# Encoder_Interface.net
KiCad netlist of a schematic drawn in Altium Designer
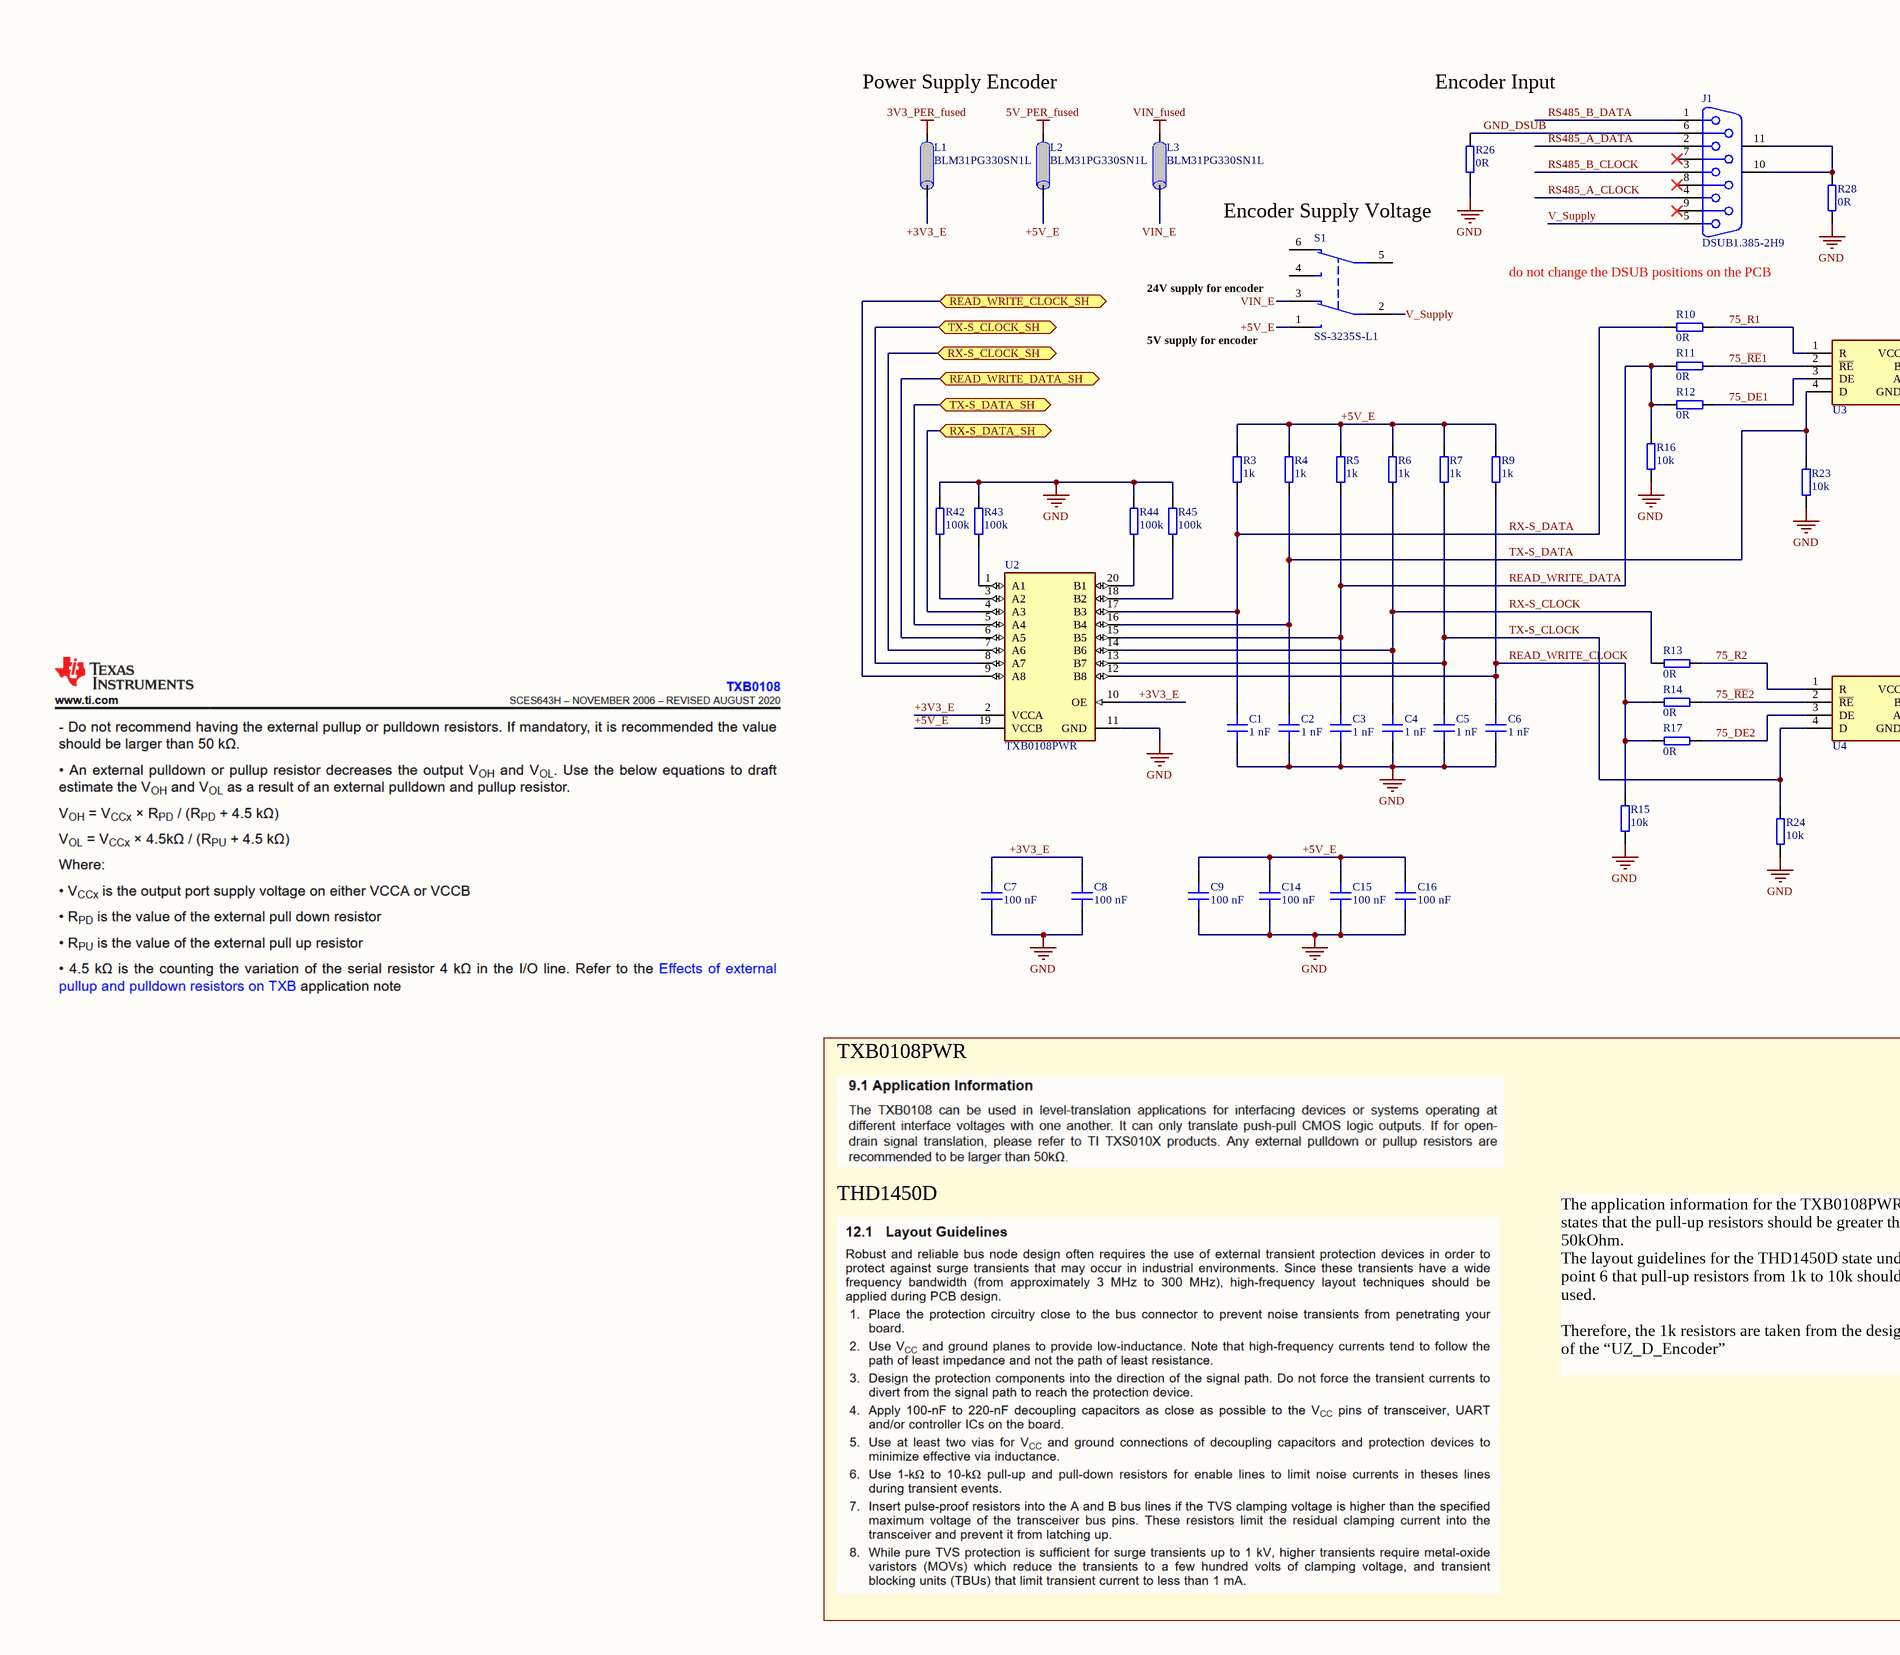
[diagram p0: Encoder_Interface.SchDoc, left]
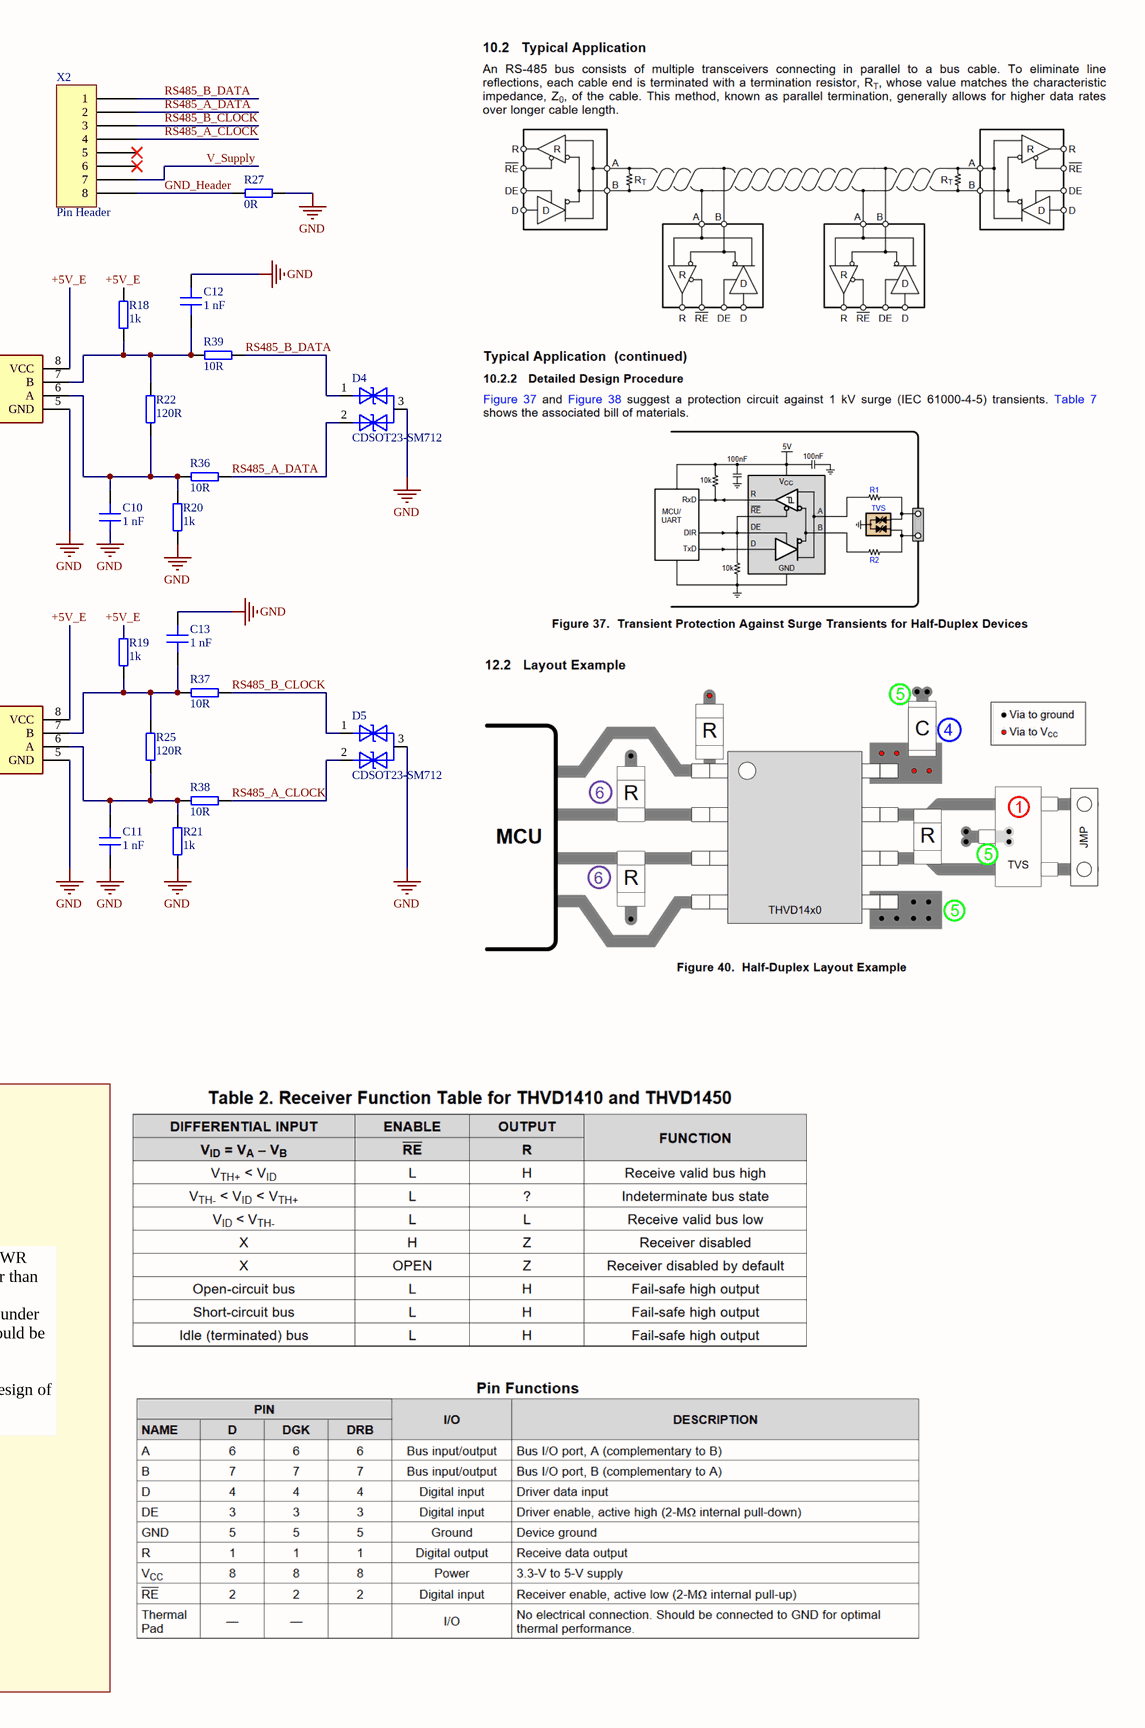
[diagram p1: Encoder_Interface.SchDoc, right]

(export (version "E")
  (design (tool "Eeschema 10.0.6"))
  (components
    (comp (ref "C1")
      (value "1 nF")
      (footprint "C_0603")
      (description "Capacitor 0603, 50 VDC, 1 nF, C0G")
      (fields
        (field (name "MANUFACTURER PART NUMBER") "06035A102JAT2A")
        (field (name "MANUFACTURER") "AVX")
        (field (name "CREATED FROM") "MGremer")
      )
      (libsource (lib "user") (part "Capacitor"))
    )
    (comp (ref "C2")
      (value "1 nF")
      (footprint "C_0603")
      (description "Capacitor 0603, 50 VDC, 1 nF, C0G")
      (fields
        (field (name "MANUFACTURER PART NUMBER") "06035A102JAT2A")
        (field (name "MANUFACTURER") "AVX")
        (field (name "CREATED FROM") "MGremer")
      )
      (libsource (lib "user") (part "Capacitor"))
    )
    (comp (ref "C3")
      (value "1 nF")
      (footprint "C_0603")
      (description "Capacitor 0603, 50 VDC, 1 nF, C0G")
      (fields
        (field (name "MANUFACTURER PART NUMBER") "06035A102JAT2A")
        (field (name "MANUFACTURER") "AVX")
        (field (name "CREATED FROM") "MGremer")
      )
      (libsource (lib "user") (part "Capacitor"))
    )
    (comp (ref "C4")
      (value "1 nF")
      (footprint "C_0603")
      (description "Capacitor 0603, 50 VDC, 1 nF, C0G")
      (fields
        (field (name "MANUFACTURER PART NUMBER") "06035A102JAT2A")
        (field (name "MANUFACTURER") "AVX")
        (field (name "CREATED FROM") "MGremer")
      )
      (libsource (lib "user") (part "Capacitor"))
    )
    (comp (ref "C5")
      (value "1 nF")
      (footprint "C_0603")
      (description "Capacitor 0603, 50 VDC, 1 nF, C0G")
      (fields
        (field (name "MANUFACTURER PART NUMBER") "06035A102JAT2A")
        (field (name "MANUFACTURER") "AVX")
        (field (name "CREATED FROM") "MGremer")
      )
      (libsource (lib "user") (part "Capacitor"))
    )
    (comp (ref "C6")
      (value "1 nF")
      (footprint "C_0603")
      (description "Capacitor 0603, 50 VDC, 1 nF, C0G")
      (fields
        (field (name "MANUFACTURER PART NUMBER") "06035A102JAT2A")
        (field (name "MANUFACTURER") "AVX")
        (field (name "CREATED FROM") "MGremer")
      )
      (libsource (lib "user") (part "Capacitor"))
    )
    (comp (ref "C7")
      (value "100 nF")
      (footprint "C_0603")
      (description "Capacitor 0603, 50 VDC, 100 nF, X7R")
      (fields
        (field (name "MANUFACTURER PART NUMBER") "CC0603KRX7R9BB104")
        (field (name "MANUFACTURER") "YAGEO")
        (field (name "CREATED FROM") "AGeiger")
      )
      (libsource (lib "user") (part "Capacitor"))
    )
    (comp (ref "C8")
      (value "100 nF")
      (footprint "C_0603")
      (description "Capacitor 0603, 50 VDC, 100 nF, X7R")
      (fields
        (field (name "MANUFACTURER PART NUMBER") "CC0603KRX7R9BB104")
        (field (name "MANUFACTURER") "YAGEO")
        (field (name "CREATED FROM") "AGeiger")
      )
      (libsource (lib "user") (part "Capacitor"))
    )
    (comp (ref "C9")
      (value "100 nF")
      (footprint "C_0603")
      (description "Capacitor 0603, 50 VDC, 100 nF, X7R")
      (fields
        (field (name "MANUFACTURER PART NUMBER") "CC0603KRX7R9BB104")
        (field (name "MANUFACTURER") "YAGEO")
        (field (name "CREATED FROM") "AGeiger")
      )
      (libsource (lib "user") (part "Capacitor"))
    )
    (comp (ref "C10")
      (value "1 nF")
      (footprint "C_0603")
      (description "Capacitor 0603, 50 VDC, 1 nF, C0G")
      (fields
        (field (name "MANUFACTURER PART NUMBER") "06035A102JAT2A")
        (field (name "MANUFACTURER") "AVX")
        (field (name "CREATED FROM") "MGremer")
      )
      (libsource (lib "user") (part "Capacitor"))
    )
    (comp (ref "C11")
      (value "1 nF")
      (footprint "C_0603")
      (description "Capacitor 0603, 50 VDC, 1 nF, C0G")
      (fields
        (field (name "MANUFACTURER PART NUMBER") "06035A102JAT2A")
        (field (name "MANUFACTURER") "AVX")
        (field (name "CREATED FROM") "MGremer")
      )
      (libsource (lib "user") (part "Capacitor"))
    )
    (comp (ref "C12")
      (value "1 nF")
      (footprint "C_0603")
      (description "Capacitor 0603, 50 VDC, 1 nF, C0G")
      (fields
        (field (name "MANUFACTURER PART NUMBER") "06035A102JAT2A")
        (field (name "MANUFACTURER") "AVX")
        (field (name "CREATED FROM") "MGremer")
      )
      (libsource (lib "user") (part "Capacitor"))
    )
    (comp (ref "C13")
      (value "1 nF")
      (footprint "C_0603")
      (description "Capacitor 0603, 50 VDC, 1 nF, C0G")
      (fields
        (field (name "MANUFACTURER PART NUMBER") "06035A102JAT2A")
        (field (name "MANUFACTURER") "AVX")
        (field (name "CREATED FROM") "MGremer")
      )
      (libsource (lib "user") (part "Capacitor"))
    )
    (comp (ref "C14")
      (value "100 nF")
      (footprint "C_0603")
      (description "Capacitor 0603, 50 VDC, 100 nF, X7R")
      (fields
        (field (name "MANUFACTURER PART NUMBER") "CC0603KRX7R9BB104")
        (field (name "MANUFACTURER") "YAGEO")
        (field (name "CREATED FROM") "AGeiger")
      )
      (libsource (lib "user") (part "Capacitor"))
    )
    (comp (ref "C15")
      (value "100 nF")
      (footprint "C_0603")
      (description "Capacitor 0603, 50 VDC, 100 nF, X7R")
      (fields
        (field (name "MANUFACTURER PART NUMBER") "CC0603KRX7R9BB104")
        (field (name "MANUFACTURER") "YAGEO")
        (field (name "CREATED FROM") "AGeiger")
      )
      (libsource (lib "user") (part "Capacitor"))
    )
    (comp (ref "C16")
      (value "100 nF")
      (footprint "C_0603")
      (description "Capacitor 0603, 50 VDC, 100 nF, X7R")
      (fields
        (field (name "MANUFACTURER PART NUMBER") "CC0603KRX7R9BB104")
        (field (name "MANUFACTURER") "YAGEO")
        (field (name "CREATED FROM") "AGeiger")
      )
      (libsource (lib "user") (part "Capacitor"))
    )
    (comp (ref "D4")
      (value "CDSOT23-SM712")
      (footprint "SOT95P230X117-3N")
      (description "TVS Diode 7V")
      (fields
        (field (name "MANUFACTURER") "Bourns")
        (field (name "VOLTAGE") "7V")
        (field (name "CREATED") "2020_09_21_MGremer")
        (field (name "CREATED FROM") "MGremer")
      )
      (libsource (lib "user") (part "CDSOT23-SM712"))
    )
    (comp (ref "D5")
      (value "CDSOT23-SM712")
      (footprint "SOT95P230X117-3N")
      (description "TVS Diode 7V")
      (fields
        (field (name "MANUFACTURER") "Bourns")
        (field (name "VOLTAGE") "7V")
        (field (name "CREATED") "2020_09_21_MGremer")
        (field (name "CREATED FROM") "MGremer")
      )
      (libsource (lib "user") (part "CDSOT23-SM712"))
    )
    (comp (ref "J1")
      (value "DSUB1.385-2H9")
      (footprint "PCB - MISC - DSUB1.385-2H9:DSUB1.385-2H9")
      (description "Connector; D Subminiature; 9 Position; Right Angle; Pitch 1.385 mm")
      (fields
        (field (name "MANUFACTURER") "TE Connectivity")
        (field (name "LCSC PART NUMBER") "C141882")
        (field (name "PUBLISHER") "Altium Limited")
        (field (name "CREATED FROM") "MHlatky")
      )
      (libsource (lib "user") (part "D Connector 9"))
    )
    (comp (ref "L1")
      (value "BLM31PG330SN1L")
      (footprint "IND 1206_3216")
      (description "9mΩ ±25% 33Ω@100MHz 6A")
      (fields
        (field (name "MANUFACTURER") "Murata Electronics")
        (field (name "LCSC PART NUMBER") "C74090")
        (field (name "CREATED FROM") "TGaupp")
      )
      (libsource (lib "user") (part "Ferrite_Bead"))
    )
    (comp (ref "L2")
      (value "BLM31PG330SN1L")
      (footprint "IND 1206_3216")
      (description "9mΩ ±25% 33Ω@100MHz 6A")
      (fields
        (field (name "MANUFACTURER") "Murata Electronics")
        (field (name "LCSC PART NUMBER") "C74090")
        (field (name "CREATED FROM") "TGaupp")
      )
      (libsource (lib "user") (part "Ferrite_Bead"))
    )
    (comp (ref "L3")
      (value "BLM31PG330SN1L")
      (footprint "IND 1206_3216")
      (description "9mΩ ±25% 33Ω@100MHz 6A")
      (fields
        (field (name "MANUFACTURER") "Murata Electronics")
        (field (name "LCSC PART NUMBER") "C74090")
        (field (name "CREATED FROM") "TGaupp")
      )
      (libsource (lib "user") (part "Ferrite_Bead"))
    )
    (comp (ref "R3")
      (value "1k")
      (footprint "RES 0603_1608")
      (description "SMD resistor E24 series")
      (fields
        (field (name "MANUFACTURER PART NUMBER") "0603WAF1001T5E")
        (field (name "MANUFACTURER") "UNI-ROYAL")
        (field (name "CREATED FROM") "AGeiger")
      )
      (libsource (lib "user") (part "Resistor"))
    )
    (comp (ref "R4")
      (value "1k")
      (footprint "RES 0603_1608")
      (description "SMD resistor E24 series")
      (fields
        (field (name "MANUFACTURER PART NUMBER") "0603WAF1001T5E")
        (field (name "MANUFACTURER") "UNI-ROYAL")
        (field (name "CREATED FROM") "AGeiger")
      )
      (libsource (lib "user") (part "Resistor"))
    )
    (comp (ref "R5")
      (value "1k")
      (footprint "RES 0603_1608")
      (description "SMD resistor E24 series")
      (fields
        (field (name "MANUFACTURER PART NUMBER") "0603WAF1001T5E")
        (field (name "MANUFACTURER") "UNI-ROYAL")
        (field (name "CREATED FROM") "AGeiger")
      )
      (libsource (lib "user") (part "Resistor"))
    )
    (comp (ref "R6")
      (value "1k")
      (footprint "RES 0603_1608")
      (description "SMD resistor E24 series")
      (fields
        (field (name "MANUFACTURER PART NUMBER") "0603WAF1001T5E")
        (field (name "MANUFACTURER") "UNI-ROYAL")
        (field (name "CREATED FROM") "AGeiger")
      )
      (libsource (lib "user") (part "Resistor"))
    )
    (comp (ref "R7")
      (value "1k")
      (footprint "RES 0603_1608")
      (description "SMD resistor E24 series")
      (fields
        (field (name "MANUFACTURER PART NUMBER") "0603WAF1001T5E")
        (field (name "MANUFACTURER") "UNI-ROYAL")
        (field (name "CREATED FROM") "AGeiger")
      )
      (libsource (lib "user") (part "Resistor"))
    )
    (comp (ref "R9")
      (value "1k")
      (footprint "RES 0603_1608")
      (description "SMD resistor E24 series")
      (fields
        (field (name "MANUFACTURER PART NUMBER") "0603WAF1001T5E")
        (field (name "MANUFACTURER") "UNI-ROYAL")
        (field (name "CREATED FROM") "AGeiger")
      )
      (libsource (lib "user") (part "Resistor"))
    )
    (comp (ref "R10")
      (value "0R")
      (footprint "RES 0603_1608")
      (description "SMD resistor E24 series")
      (fields
        (field (name "MANUFACTURER PART NUMBER") "RC0603JR-070RL")
        (field (name "MANUFACTURER") "YAGEO")
        (field (name "CREATED FROM") "MGremer")
      )
      (libsource (lib "user") (part "Resistor"))
    )
    (comp (ref "R11")
      (value "0R")
      (footprint "RES 0603_1608")
      (description "SMD resistor E24 series")
      (fields
        (field (name "MANUFACTURER PART NUMBER") "RC0603JR-070RL")
        (field (name "MANUFACTURER") "YAGEO")
        (field (name "CREATED FROM") "MGremer")
      )
      (libsource (lib "user") (part "Resistor"))
    )
    (comp (ref "R12")
      (value "0R")
      (footprint "RES 0603_1608")
      (description "SMD resistor E24 series")
      (fields
        (field (name "MANUFACTURER PART NUMBER") "RC0603JR-070RL")
        (field (name "MANUFACTURER") "YAGEO")
        (field (name "CREATED FROM") "MGremer")
      )
      (libsource (lib "user") (part "Resistor"))
    )
    (comp (ref "R13")
      (value "0R")
      (footprint "RES 0603_1608")
      (description "SMD resistor E24 series")
      (fields
        (field (name "MANUFACTURER PART NUMBER") "RC0603JR-070RL")
        (field (name "MANUFACTURER") "YAGEO")
        (field (name "CREATED FROM") "MGremer")
      )
      (libsource (lib "user") (part "Resistor"))
    )
    (comp (ref "R14")
      (value "0R")
      (footprint "RES 0603_1608")
      (description "SMD resistor E24 series")
      (fields
        (field (name "MANUFACTURER PART NUMBER") "RC0603JR-070RL")
        (field (name "MANUFACTURER") "YAGEO")
        (field (name "CREATED FROM") "MGremer")
      )
      (libsource (lib "user") (part "Resistor"))
    )
    (comp (ref "R15")
      (value "10k")
      (footprint "RES 0603_1608")
      (description "SMD resistor E24 series")
      (fields
        (field (name "MANUFACTURER PART NUMBER") "RK73B1JTTD103J")
        (field (name "MANUFACTURER") "KOA Speer")
        (field (name "CREATED FROM") "MGremer")
      )
      (libsource (lib "user") (part "Resistor"))
    )
    (comp (ref "R16")
      (value "10k")
      (footprint "RES 0603_1608")
      (description "SMD resistor E24 series")
      (fields
        (field (name "MANUFACTURER PART NUMBER") "RK73B1JTTD103J")
        (field (name "MANUFACTURER") "KOA Speer")
        (field (name "CREATED FROM") "MGremer")
      )
      (libsource (lib "user") (part "Resistor"))
    )
    (comp (ref "R17")
      (value "0R")
      (footprint "RES 0603_1608")
      (description "SMD resistor E24 series")
      (fields
        (field (name "MANUFACTURER PART NUMBER") "RC0603JR-070RL")
        (field (name "MANUFACTURER") "YAGEO")
        (field (name "CREATED FROM") "MGremer")
      )
      (libsource (lib "user") (part "Resistor"))
    )
    (comp (ref "R18")
      (value "1k")
      (footprint "RES 0603_1608")
      (description "SMD resistor E24 series")
      (fields
        (field (name "MANUFACTURER PART NUMBER") "0603WAF1001T5E")
        (field (name "MANUFACTURER") "UNI-ROYAL")
        (field (name "CREATED FROM") "AGeiger")
      )
      (libsource (lib "user") (part "Resistor"))
    )
    (comp (ref "R19")
      (value "1k")
      (footprint "RES 0603_1608")
      (description "SMD resistor E24 series")
      (fields
        (field (name "MANUFACTURER PART NUMBER") "0603WAF1001T5E")
        (field (name "MANUFACTURER") "UNI-ROYAL")
        (field (name "CREATED FROM") "AGeiger")
      )
      (libsource (lib "user") (part "Resistor"))
    )
    (comp (ref "R20")
      (value "1k")
      (footprint "RES 0603_1608")
      (description "SMD resistor E24 series")
      (fields
        (field (name "MANUFACTURER PART NUMBER") "0603WAF1001T5E")
        (field (name "MANUFACTURER") "UNI-ROYAL")
        (field (name "CREATED FROM") "AGeiger")
      )
      (libsource (lib "user") (part "Resistor"))
    )
    (comp (ref "R21")
      (value "1k")
      (footprint "RES 0603_1608")
      (description "SMD resistor E24 series")
      (fields
        (field (name "MANUFACTURER PART NUMBER") "0603WAF1001T5E")
        (field (name "MANUFACTURER") "UNI-ROYAL")
        (field (name "CREATED FROM") "AGeiger")
      )
      (libsource (lib "user") (part "Resistor"))
    )
    (comp (ref "R22")
      (value "120R")
      (footprint "RES 0603_1608")
      (description "SMD resistor E24 series")
      (fields
        (field (name "MANUFACTURER PART NUMBER") "RK73B1JTTD121J")
        (field (name "MANUFACTURER") "KOA Speer")
        (field (name "CREATED FROM") "MGremer")
      )
      (libsource (lib "user") (part "Resistor"))
    )
    (comp (ref "R23")
      (value "10k")
      (footprint "RES 0603_1608")
      (description "SMD resistor E24 series")
      (fields
        (field (name "MANUFACTURER PART NUMBER") "RK73B1JTTD103J")
        (field (name "MANUFACTURER") "KOA Speer")
        (field (name "CREATED FROM") "MGremer")
      )
      (libsource (lib "user") (part "Resistor"))
    )
    (comp (ref "R24")
      (value "10k")
      (footprint "RES 0603_1608")
      (description "SMD resistor E24 series")
      (fields
        (field (name "MANUFACTURER PART NUMBER") "RK73B1JTTD103J")
        (field (name "MANUFACTURER") "KOA Speer")
        (field (name "CREATED FROM") "MGremer")
      )
      (libsource (lib "user") (part "Resistor"))
    )
    (comp (ref "R25")
      (value "120R")
      (footprint "RES 0603_1608")
      (description "SMD resistor E24 series")
      (fields
        (field (name "MANUFACTURER PART NUMBER") "RK73B1JTTD121J")
        (field (name "MANUFACTURER") "KOA Speer")
        (field (name "CREATED FROM") "MGremer")
      )
      (libsource (lib "user") (part "Resistor"))
    )
    (comp (ref "R26")
      (value "0R")
      (footprint "RES 0603_1608")
      (description "SMD resistor E24 series")
      (fields
        (field (name "MANUFACTURER PART NUMBER") "RC0603JR-070RL")
        (field (name "MANUFACTURER") "YAGEO")
        (field (name "CREATED FROM") "MGremer")
      )
      (libsource (lib "user") (part "Resistor"))
    )
    (comp (ref "R27")
      (value "0R")
      (footprint "RES 0603_1608")
      (description "SMD resistor E24 series")
      (fields
        (field (name "MANUFACTURER PART NUMBER") "RC0603JR-070RL")
        (field (name "MANUFACTURER") "YAGEO")
        (field (name "CREATED FROM") "MGremer")
      )
      (libsource (lib "user") (part "Resistor"))
    )
    (comp (ref "R28")
      (value "0R")
      (footprint "RES 0603_1608")
      (description "SMD resistor E24 series")
      (fields
        (field (name "MANUFACTURER PART NUMBER") "RC0603JR-070RL")
        (field (name "MANUFACTURER") "YAGEO")
        (field (name "CREATED FROM") "MGremer")
      )
      (libsource (lib "user") (part "Resistor"))
    )
    (comp (ref "R36")
      (value "10R")
      (footprint "RES 0603_1608")
      (description "SMD 1/10watt 10ohms 1%")
      (fields
        (field (name "MANUFACTURER PART NUMBER") "CRCW060310R0FKTA")
        (field (name "MANUFACTURER") "Vishay")
        (field (name "CREATED FROM") "TGaupp")
      )
      (libsource (lib "user") (part "Resistor"))
    )
    (comp (ref "R37")
      (value "10R")
      (footprint "RES 0603_1608")
      (description "SMD 1/10watt 10ohms 1%")
      (fields
        (field (name "MANUFACTURER PART NUMBER") "CRCW060310R0FKTA")
        (field (name "MANUFACTURER") "Vishay")
        (field (name "CREATED FROM") "TGaupp")
      )
      (libsource (lib "user") (part "Resistor"))
    )
    (comp (ref "R38")
      (value "10R")
      (footprint "RES 0603_1608")
      (description "SMD 1/10watt 10ohms 1%")
      (fields
        (field (name "MANUFACTURER PART NUMBER") "CRCW060310R0FKTA")
        (field (name "MANUFACTURER") "Vishay")
        (field (name "CREATED FROM") "TGaupp")
      )
      (libsource (lib "user") (part "Resistor"))
    )
    (comp (ref "R39")
      (value "10R")
      (footprint "RES 0603_1608")
      (description "SMD 1/10watt 10ohms 1%")
      (fields
        (field (name "MANUFACTURER PART NUMBER") "CRCW060310R0FKTA")
        (field (name "MANUFACTURER") "Vishay")
        (field (name "CREATED FROM") "TGaupp")
      )
      (libsource (lib "user") (part "Resistor"))
    )
    (comp (ref "R42")
      (value "100k")
      (footprint "RES 0603_1608")
      (description "SMD resistor E24 series")
      (fields
        (field (name "MANUFACTURER PART NUMBER") "RK73B1JTTD104J")
        (field (name "MANUFACTURER") "KOA Speer")
        (field (name "CREATED FROM") "MGremer")
      )
      (libsource (lib "user") (part "Resistor"))
    )
    (comp (ref "R43")
      (value "100k")
      (footprint "RES 0603_1608")
      (description "SMD resistor E24 series")
      (fields
        (field (name "MANUFACTURER PART NUMBER") "RK73B1JTTD104J")
        (field (name "MANUFACTURER") "KOA Speer")
        (field (name "CREATED FROM") "MGremer")
      )
      (libsource (lib "user") (part "Resistor"))
    )
    (comp (ref "R44")
      (value "100k")
      (footprint "RES 0603_1608")
      (description "SMD resistor E24 series")
      (fields
        (field (name "MANUFACTURER PART NUMBER") "RK73B1JTTD104J")
        (field (name "MANUFACTURER") "KOA Speer")
        (field (name "CREATED FROM") "MGremer")
      )
      (libsource (lib "user") (part "Resistor"))
    )
    (comp (ref "R45")
      (value "100k")
      (footprint "RES 0603_1608")
      (description "SMD resistor E24 series")
      (fields
        (field (name "MANUFACTURER PART NUMBER") "RK73B1JTTD104J")
        (field (name "MANUFACTURER") "KOA Speer")
        (field (name "CREATED FROM") "MGremer")
      )
      (libsource (lib "user") (part "Resistor"))
    )
    (comp (ref "S1")
      (value "SS-3235S-L1")
      (footprint "SS-3235S-L1")
      (description "50mA Horizontal attachment DPDT 12V 12V 50mA 10,000 times Black SMD Slide Switches ROHS")
      (fields
        (field (name "MANUFACTURER") "XKB Connection")
        (field (name "LCSC PART NUMBER") "C500055")
        (field (name "CREATED FROM") "AGeiger")
      )
      (libsource (lib "user") (part "SS-3235S-L1"))
    )
    (comp (ref "U2")
      (value "TXB0108PWR")
      (footprint "SOP65P640X120-20N")
      (description "Voltage Levels 8-Bit Bi-directional V-Level Translator")
      (fields
        (field (name "MANUFACTURER") "Texas Instruments")
        (field (name "LCSC PART NUMBER") "C53406")
        (field (name "CREATED FROM") "T.Gaupp")
      )
      (libsource (lib "user") (part "TXB0108PWR"))
    )
    (comp (ref "U3")
      (value "THVD1450DR")
      (footprint "SOIC127P600X175-8N")
      (description "3.3-V to 5-V RS-485 transceiver with +/-18-kV IEC ESD protection 8-SOIC -40 to 125")
      (fields
        (field (name "MANUFACTURER") "Texas Instruments")
        (field (name "LCSC PART NUMBER") "C2671361")
        (field (name "CREATED FROM") "TGaupp")
      )
      (libsource (lib "user") (part "THVD1450D"))
    )
    (comp (ref "U4")
      (value "THVD1450DR")
      (footprint "SOIC127P600X175-8N")
      (description "3.3-V to 5-V RS-485 transceiver with +/-18-kV IEC ESD protection 8-SOIC -40 to 125")
      (fields
        (field (name "MANUFACTURER") "Texas Instruments")
        (field (name "LCSC PART NUMBER") "C2671361")
        (field (name "CREATED FROM") "TGaupp")
      )
      (libsource (lib "user") (part "THVD1450D"))
    )
    (comp (ref "X2")
      (value "Pin Header")
      (footprint "HDR1X8")
      (description "8 Pin")
      (fields
        (field (name "MANUFACTURER PART NUMBER") "103741-8")
        (field (name "MANUFACTURER") "TE Connectivity")
        (field (name "CREATED FROM") "MHlatky")
      )
      (libsource (lib "user") (part "8 Pin"))
    )
  )
  (nets
    (net (code "1") (name "/+3V3_E") (class "Default")
      (node (ref "C7") (pin "2") (pinfunction "2_2") (pintype "passive"))
      (node (ref "C8") (pin "2") (pinfunction "2_2") (pintype "passive"))
      (node (ref "L1") (pin "2") (pinfunction "2_2") (pintype "passive"))
      (node (ref "U2") (pin "10") (pinfunction "OE_10") (pintype "input"))
      (node (ref "U2") (pin "2") (pinfunction "VCCA_2") (pintype "power_in"))
    )
    (net (code "2") (name "/+5V_E") (class "Default")
      (node (ref "C14") (pin "2") (pinfunction "2_2") (pintype "passive"))
      (node (ref "C15") (pin "2") (pinfunction "2_2") (pintype "passive"))
      (node (ref "C16") (pin "2") (pinfunction "2_2") (pintype "passive"))
      (node (ref "C9") (pin "2") (pinfunction "2_2") (pintype "passive"))
      (node (ref "L2") (pin "2") (pinfunction "2_2") (pintype "passive"))
      (node (ref "R18") (pin "2") (pinfunction "2_2") (pintype "passive"))
      (node (ref "R19") (pin "2") (pinfunction "2_2") (pintype "passive"))
      (node (ref "R3") (pin "2") (pinfunction "2_2") (pintype "passive"))
      (node (ref "R4") (pin "2") (pinfunction "2_2") (pintype "passive"))
      (node (ref "R5") (pin "2") (pinfunction "2_2") (pintype "passive"))
      (node (ref "R6") (pin "2") (pinfunction "2_2") (pintype "passive"))
      (node (ref "R7") (pin "2") (pinfunction "2_2") (pintype "passive"))
      (node (ref "R9") (pin "2") (pinfunction "2_2") (pintype "passive"))
      (node (ref "S1") (pin "1") (pinfunction "NO1_1") (pintype "passive"))
      (node (ref "U2") (pin "19") (pinfunction "VCCB_19") (pintype "power_in"))
      (node (ref "U3") (pin "8") (pinfunction "VCC_8") (pintype "passive"))
      (node (ref "U4") (pin "8") (pinfunction "VCC_8") (pintype "passive"))
    )
    (net (code "3") (name "/75_DE1") (class "Default")
      (node (ref "R12") (pin "2") (pinfunction "2_2") (pintype "passive"))
      (node (ref "U3") (pin "3") (pinfunction "DE_3") (pintype "passive"))
    )
    (net (code "4") (name "/75_DE2") (class "Default")
      (node (ref "R17") (pin "2") (pinfunction "2_2") (pintype "passive"))
      (node (ref "U4") (pin "3") (pinfunction "DE_3") (pintype "passive"))
    )
    (net (code "5") (name "/75_R1") (class "Default")
      (node (ref "R10") (pin "2") (pinfunction "2_2") (pintype "passive"))
      (node (ref "U3") (pin "1") (pinfunction "R_1") (pintype "passive"))
    )
    (net (code "6") (name "/75_R2") (class "Default")
      (node (ref "R13") (pin "2") (pinfunction "2_2") (pintype "passive"))
      (node (ref "U4") (pin "1") (pinfunction "R_1") (pintype "passive"))
    )
    (net (code "7") (name "/75_~{RE}1") (class "Default")
      (node (ref "R11") (pin "2") (pinfunction "2_2") (pintype "passive"))
      (node (ref "U3") (pin "2") (pinfunction "~{RE}_2") (pintype "passive"))
    )
    (net (code "8") (name "/75_~{RE}2") (class "Default")
      (node (ref "R14") (pin "2") (pinfunction "2_2") (pintype "passive"))
      (node (ref "U4") (pin "2") (pinfunction "~{RE}_2") (pintype "passive"))
    )
    (net (code "9") (name "/GND_DSUB") (class "Default")
      (node (ref "J1") (pin "6") (pinfunction "6_6") (pintype "passive"))
      (node (ref "R26") (pin "1") (pinfunction "1_1") (pintype "passive"))
    )
    (net (code "10") (name "/GND_Header") (class "Default")
      (node (ref "R27") (pin "1") (pinfunction "1_1") (pintype "passive"))
      (node (ref "X2") (pin "8") (pinfunction "8_8") (pintype "passive"))
    )
    (net (code "11") (name "/READ_WRITE_CLOCK") (class "Default")
      (node (ref "C6") (pin "2") (pinfunction "2_2") (pintype "passive"))
      (node (ref "R14") (pin "1") (pinfunction "1_1") (pintype "passive"))
      (node (ref "R15") (pin "2") (pinfunction "2_2") (pintype "passive"))
      (node (ref "R17") (pin "1") (pinfunction "1_1") (pintype "passive"))
      (node (ref "R9") (pin "1") (pinfunction "1_1") (pintype "passive"))
      (node (ref "U2") (pin "12") (pinfunction "B8_12") (pintype "bidirectional"))
    )
    (net (code "12") (name "/READ_WRITE_CLOCK_SH") (class "Default")
      (node (ref "U2") (pin "9") (pinfunction "A8_9") (pintype "bidirectional"))
    )
    (net (code "13") (name "/READ_WRITE_DATA") (class "Default")
      (node (ref "C3") (pin "2") (pinfunction "2_2") (pintype "passive"))
      (node (ref "R11") (pin "1") (pinfunction "1_1") (pintype "passive"))
      (node (ref "R12") (pin "1") (pinfunction "1_1") (pintype "passive"))
      (node (ref "R16") (pin "2") (pinfunction "2_2") (pintype "passive"))
      (node (ref "R5") (pin "1") (pinfunction "1_1") (pintype "passive"))
      (node (ref "U2") (pin "15") (pinfunction "B5_15") (pintype "bidirectional"))
    )
    (net (code "14") (name "/READ_WRITE_DATA_SH") (class "Default")
      (node (ref "U2") (pin "6") (pinfunction "A5_6") (pintype "bidirectional"))
    )
    (net (code "15") (name "/RS485_A_CLOCK") (class "Default")
      (node (ref "D5") (pin "2") (pinfunction "K2_2") (pintype "passive"))
      (node (ref "J1") (pin "4") (pinfunction "4_4") (pintype "passive"))
      (node (ref "R38") (pin "2") (pinfunction "2_2") (pintype "passive"))
      (node (ref "X2") (pin "4") (pinfunction "4_4") (pintype "passive"))
    )
    (net (code "16") (name "/RS485_A_DATA") (class "Default")
      (node (ref "D4") (pin "2") (pinfunction "K2_2") (pintype "passive"))
      (node (ref "J1") (pin "2") (pinfunction "2_2") (pintype "passive"))
      (node (ref "R36") (pin "2") (pinfunction "2_2") (pintype "passive"))
      (node (ref "X2") (pin "2") (pinfunction "2_2") (pintype "passive"))
    )
    (net (code "17") (name "/RS485_B_CLOCK") (class "Default")
      (node (ref "D5") (pin "1") (pinfunction "K1_1") (pintype "passive"))
      (node (ref "J1") (pin "3") (pinfunction "3_3") (pintype "passive"))
      (node (ref "R37") (pin "2") (pinfunction "2_2") (pintype "passive"))
      (node (ref "X2") (pin "3") (pinfunction "3_3") (pintype "passive"))
    )
    (net (code "18") (name "/RS485_B_DATA") (class "Default")
      (node (ref "D4") (pin "1") (pinfunction "K1_1") (pintype "passive"))
      (node (ref "J1") (pin "1") (pinfunction "1_1") (pintype "passive"))
      (node (ref "R39") (pin "2") (pinfunction "2_2") (pintype "passive"))
      (node (ref "X2") (pin "1") (pinfunction "1_1") (pintype "passive"))
    )
    (net (code "19") (name "/RX-S_CLOCK") (class "Default")
      (node (ref "C4") (pin "2") (pinfunction "2_2") (pintype "passive"))
      (node (ref "R13") (pin "1") (pinfunction "1_1") (pintype "passive"))
      (node (ref "R6") (pin "1") (pinfunction "1_1") (pintype "passive"))
      (node (ref "U2") (pin "14") (pinfunction "B6_14") (pintype "bidirectional"))
    )
    (net (code "20") (name "/RX-S_CLOCK_SH") (class "Default")
      (node (ref "U2") (pin "7") (pinfunction "A6_7") (pintype "bidirectional"))
    )
    (net (code "21") (name "/RX-S_DATA") (class "Default")
      (node (ref "C1") (pin "2") (pinfunction "2_2") (pintype "passive"))
      (node (ref "R10") (pin "1") (pinfunction "1_1") (pintype "passive"))
      (node (ref "R3") (pin "1") (pinfunction "1_1") (pintype "passive"))
      (node (ref "U2") (pin "17") (pinfunction "B3_17") (pintype "bidirectional"))
    )
    (net (code "22") (name "/RX-S_DATA_SH") (class "Default")
      (node (ref "U2") (pin "4") (pinfunction "A3_4") (pintype "bidirectional"))
    )
    (net (code "23") (name "/TX-S_CLOCK") (class "Default")
      (node (ref "C5") (pin "2") (pinfunction "2_2") (pintype "passive"))
      (node (ref "R24") (pin "2") (pinfunction "2_2") (pintype "passive"))
      (node (ref "R7") (pin "1") (pinfunction "1_1") (pintype "passive"))
      (node (ref "U2") (pin "13") (pinfunction "B7_13") (pintype "bidirectional"))
      (node (ref "U4") (pin "4") (pinfunction "D_4") (pintype "passive"))
    )
    (net (code "24") (name "/TX-S_CLOCK_SH") (class "Default")
      (node (ref "U2") (pin "8") (pinfunction "A7_8") (pintype "bidirectional"))
    )
    (net (code "25") (name "/TX-S_DATA") (class "Default")
      (node (ref "C2") (pin "2") (pinfunction "2_2") (pintype "passive"))
      (node (ref "R23") (pin "2") (pinfunction "2_2") (pintype "passive"))
      (node (ref "R4") (pin "1") (pinfunction "1_1") (pintype "passive"))
      (node (ref "U2") (pin "16") (pinfunction "B4_16") (pintype "bidirectional"))
      (node (ref "U3") (pin "4") (pinfunction "D_4") (pintype "passive"))
    )
    (net (code "26") (name "/TX-S_DATA_SH") (class "Default")
      (node (ref "U2") (pin "5") (pinfunction "A4_5") (pintype "bidirectional"))
    )
    (net (code "27") (name "/VIN_E") (class "Default")
      (node (ref "L3") (pin "2") (pinfunction "2_2") (pintype "passive"))
      (node (ref "S1") (pin "3") (pinfunction "NC1_3") (pintype "passive"))
    )
    (net (code "28") (name "/V_Supply") (class "Default")
      (node (ref "J1") (pin "5") (pinfunction "5_5") (pintype "passive"))
      (node (ref "S1") (pin "2") (pinfunction "COM1_2") (pintype "passive"))
      (node (ref "X2") (pin "7") (pinfunction "7_7") (pintype "passive"))
    )
    (net (code "29") (name "3V3_PER_fused") (class "Default")
      (node (ref "L1") (pin "1") (pinfunction "1_1") (pintype "passive"))
    )
    (net (code "30") (name "5V_PER_fused") (class "Default")
      (node (ref "L2") (pin "1") (pinfunction "1_1") (pintype "passive"))
    )
    (net (code "31") (name "GND") (class "Default")
      (node (ref "C1") (pin "1") (pinfunction "1_1") (pintype "passive"))
      (node (ref "C10") (pin "1") (pinfunction "1_1") (pintype "passive"))
      (node (ref "C11") (pin "1") (pinfunction "1_1") (pintype "passive"))
      (node (ref "C12") (pin "2") (pinfunction "2_2") (pintype "passive"))
      (node (ref "C13") (pin "2") (pinfunction "2_2") (pintype "passive"))
      (node (ref "C14") (pin "1") (pinfunction "1_1") (pintype "passive"))
      (node (ref "C15") (pin "1") (pinfunction "1_1") (pintype "passive"))
      (node (ref "C16") (pin "1") (pinfunction "1_1") (pintype "passive"))
      (node (ref "C2") (pin "1") (pinfunction "1_1") (pintype "passive"))
      (node (ref "C3") (pin "1") (pinfunction "1_1") (pintype "passive"))
      (node (ref "C4") (pin "1") (pinfunction "1_1") (pintype "passive"))
      (node (ref "C5") (pin "1") (pinfunction "1_1") (pintype "passive"))
      (node (ref "C6") (pin "1") (pinfunction "1_1") (pintype "passive"))
      (node (ref "C7") (pin "1") (pinfunction "1_1") (pintype "passive"))
      (node (ref "C8") (pin "1") (pinfunction "1_1") (pintype "passive"))
      (node (ref "C9") (pin "1") (pinfunction "1_1") (pintype "passive"))
      (node (ref "D4") (pin "3") (pinfunction "A_3") (pintype "passive"))
      (node (ref "D5") (pin "3") (pinfunction "A_3") (pintype "passive"))
      (node (ref "R15") (pin "1") (pinfunction "1_1") (pintype "passive"))
      (node (ref "R16") (pin "1") (pinfunction "1_1") (pintype "passive"))
      (node (ref "R20") (pin "1") (pinfunction "1_1") (pintype "passive"))
      (node (ref "R21") (pin "1") (pinfunction "1_1") (pintype "passive"))
      (node (ref "R23") (pin "1") (pinfunction "1_1") (pintype "passive"))
      (node (ref "R24") (pin "1") (pinfunction "1_1") (pintype "passive"))
      (node (ref "R26") (pin "2") (pinfunction "2_2") (pintype "passive"))
      (node (ref "R27") (pin "2") (pinfunction "2_2") (pintype "passive"))
      (node (ref "R28") (pin "1") (pinfunction "1_1") (pintype "passive"))
      (node (ref "R42") (pin "2") (pinfunction "2_2") (pintype "passive"))
      (node (ref "R43") (pin "2") (pinfunction "2_2") (pintype "passive"))
      (node (ref "R44") (pin "2") (pinfunction "2_2") (pintype "passive"))
      (node (ref "R45") (pin "2") (pinfunction "2_2") (pintype "passive"))
      (node (ref "U2") (pin "11") (pinfunction "GND_11") (pintype "passive"))
      (node (ref "U3") (pin "5") (pinfunction "GND_5") (pintype "passive"))
      (node (ref "U4") (pin "5") (pinfunction "GND_5") (pintype "passive"))
    )
    (net (code "32") (name "Net-(J1-MH1)") (class "Default")
      (node (ref "J1") (pin "10") (pinfunction "MH1_10") (pintype "passive"))
      (node (ref "J1") (pin "11") (pinfunction "MH2_11") (pintype "passive"))
      (node (ref "R28") (pin "2") (pinfunction "2_2") (pintype "passive"))
    )
    (net (code "33") (name "Net-(U2-A1)") (class "Default")
      (node (ref "R43") (pin "1") (pinfunction "1_1") (pintype "passive"))
      (node (ref "U2") (pin "1") (pinfunction "A1_1") (pintype "bidirectional"))
    )
    (net (code "34") (name "Net-(U2-A2)") (class "Default")
      (node (ref "R42") (pin "1") (pinfunction "1_1") (pintype "passive"))
      (node (ref "U2") (pin "3") (pinfunction "A2_3") (pintype "bidirectional"))
    )
    (net (code "35") (name "Net-(U2-B1)") (class "Default")
      (node (ref "R44") (pin "1") (pinfunction "1_1") (pintype "passive"))
      (node (ref "U2") (pin "20") (pinfunction "B1_20") (pintype "bidirectional"))
    )
    (net (code "36") (name "Net-(U2-B2)") (class "Default")
      (node (ref "R45") (pin "1") (pinfunction "1_1") (pintype "passive"))
      (node (ref "U2") (pin "18") (pinfunction "B2_18") (pintype "bidirectional"))
    )
    (net (code "37") (name "Net-(U3-A)") (class "Default")
      (node (ref "C10") (pin "2") (pinfunction "2_2") (pintype "passive"))
      (node (ref "R20") (pin "2") (pinfunction "2_2") (pintype "passive"))
      (node (ref "R22") (pin "1") (pinfunction "1_1") (pintype "passive"))
      (node (ref "R36") (pin "1") (pinfunction "1_1") (pintype "passive"))
      (node (ref "U3") (pin "6") (pinfunction "A_6") (pintype "passive"))
    )
    (net (code "38") (name "Net-(U3-B)") (class "Default")
      (node (ref "C12") (pin "1") (pinfunction "1_1") (pintype "passive"))
      (node (ref "R18") (pin "1") (pinfunction "1_1") (pintype "passive"))
      (node (ref "R22") (pin "2") (pinfunction "2_2") (pintype "passive"))
      (node (ref "R39") (pin "1") (pinfunction "1_1") (pintype "passive"))
      (node (ref "U3") (pin "7") (pinfunction "B_7") (pintype "passive"))
    )
    (net (code "39") (name "Net-(U4-A)") (class "Default")
      (node (ref "C11") (pin "2") (pinfunction "2_2") (pintype "passive"))
      (node (ref "R21") (pin "2") (pinfunction "2_2") (pintype "passive"))
      (node (ref "R25") (pin "1") (pinfunction "1_1") (pintype "passive"))
      (node (ref "R38") (pin "1") (pinfunction "1_1") (pintype "passive"))
      (node (ref "U4") (pin "6") (pinfunction "A_6") (pintype "passive"))
    )
    (net (code "40") (name "Net-(U4-B)") (class "Default")
      (node (ref "C13") (pin "1") (pinfunction "1_1") (pintype "passive"))
      (node (ref "R19") (pin "1") (pinfunction "1_1") (pintype "passive"))
      (node (ref "R25") (pin "2") (pinfunction "2_2") (pintype "passive"))
      (node (ref "R37") (pin "1") (pinfunction "1_1") (pintype "passive"))
      (node (ref "U4") (pin "7") (pinfunction "B_7") (pintype "passive"))
    )
    (net (code "41") (name "VIN_fused") (class "Default")
      (node (ref "L3") (pin "1") (pinfunction "1_1") (pintype "passive"))
    )
    (net (code "42") (name "unconnected-(J1-Pad7)") (class "Default")
      (node (ref "J1") (pin "7") (pinfunction "7_7") (pintype "passive+no_connect"))
    )
    (net (code "43") (name "unconnected-(J1-Pad8)") (class "Default")
      (node (ref "J1") (pin "8") (pinfunction "8_8") (pintype "passive+no_connect"))
    )
    (net (code "44") (name "unconnected-(J1-Pad9)") (class "Default")
      (node (ref "J1") (pin "9") (pinfunction "9_9") (pintype "passive+no_connect"))
    )
    (net (code "45") (name "unconnected-(S1-COM2-Pad5)") (class "Default")
      (node (ref "S1") (pin "5") (pinfunction "COM2_5") (pintype "passive"))
    )
    (net (code "46") (name "unconnected-(S1-NC2-Pad6)") (class "Default")
      (node (ref "S1") (pin "6") (pinfunction "NC2_6") (pintype "passive"))
    )
    (net (code "47") (name "unconnected-(S1-NO2-Pad4)") (class "Default")
      (node (ref "S1") (pin "4") (pinfunction "NO2_4") (pintype "passive"))
    )
    (net (code "48") (name "unconnected-(X2-Pad5)") (class "Default")
      (node (ref "X2") (pin "5") (pinfunction "5_5") (pintype "passive+no_connect"))
    )
    (net (code "49") (name "unconnected-(X2-Pad6)") (class "Default")
      (node (ref "X2") (pin "6") (pinfunction "6_6") (pintype "passive+no_connect"))
    )
  )
)
